# M700B.net
KiCad netlist of a schematic drawn in EAGLE
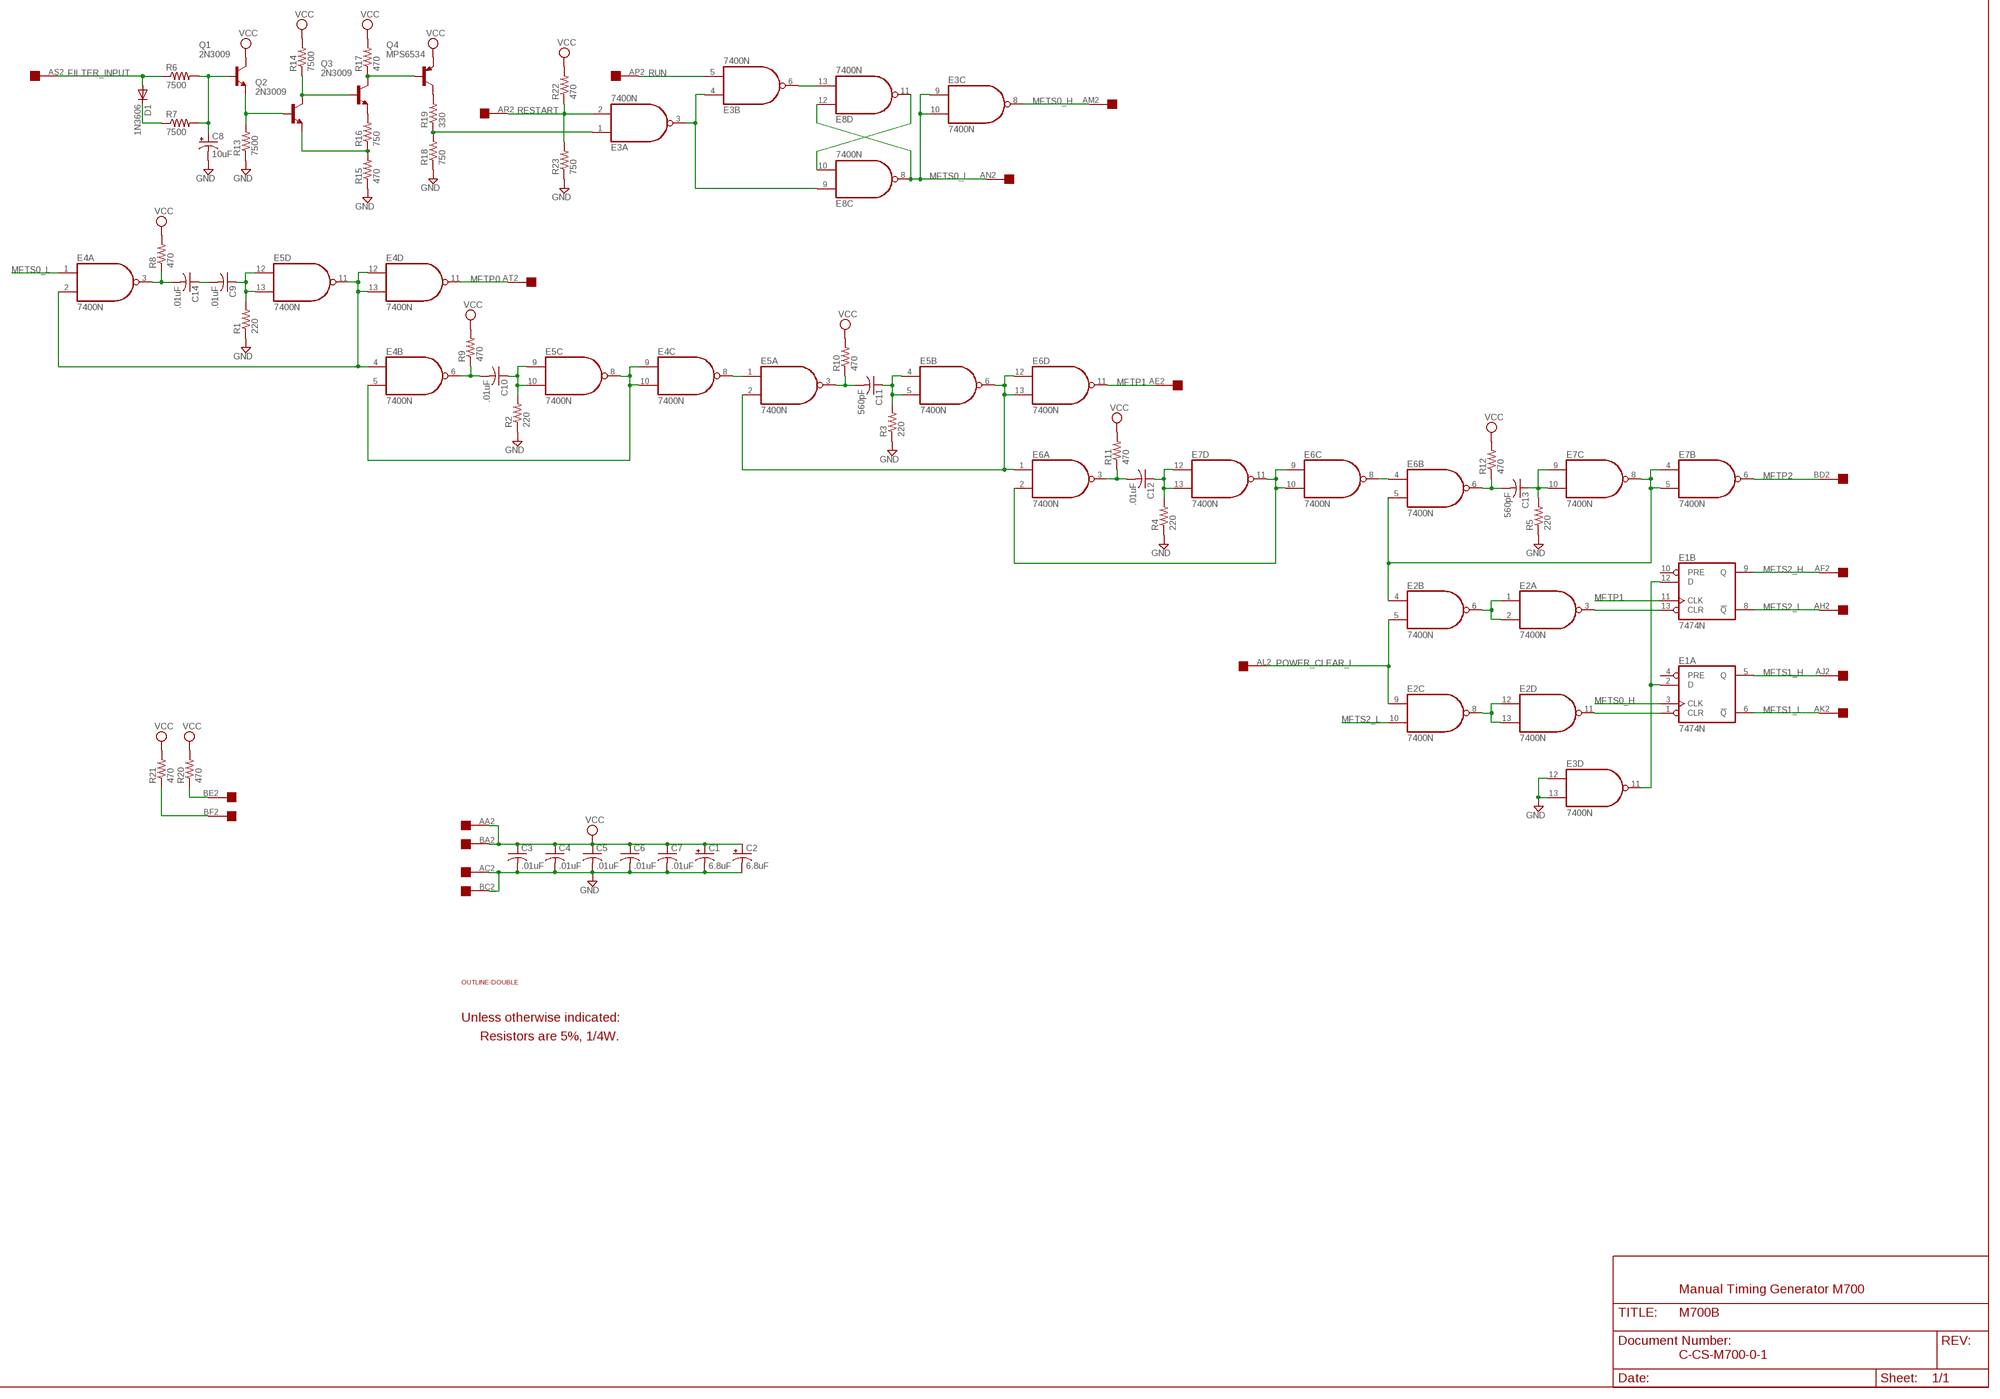
[diagram p0: schematic, sheet 1]

(export (version "E")
  (design (tool "Eeschema 10.0.6"))
  (components
    (comp (ref "C1")
      (value "6.8uF")
      (footprint "eagle-import:E12-8")
      (libsource (lib "eagle-import") (part "CPOL-USE20-8AXIAL"))
    )
    (comp (ref "C2")
      (value "6.8uF")
      (footprint "eagle-import:E12-8")
      (libsource (lib "eagle-import") (part "CPOL-USE20-8AXIAL"))
    )
    (comp (ref "C3")
      (value ".01uF")
      (footprint "eagle-import:C050-025X075")
      (libsource (lib "eagle-import") (part "C-US050-025X075"))
    )
    (comp (ref "C4")
      (value ".01uF")
      (footprint "eagle-import:C050-025X075")
      (libsource (lib "eagle-import") (part "C-US050-025X075"))
    )
    (comp (ref "C5")
      (value ".01uF")
      (footprint "eagle-import:C050-025X075")
      (libsource (lib "eagle-import") (part "C-US050-025X075"))
    )
    (comp (ref "C6")
      (value ".01uF")
      (footprint "eagle-import:C050-025X075")
      (libsource (lib "eagle-import") (part "C-US050-025X075"))
    )
    (comp (ref "C7")
      (value ".01uF")
      (footprint "eagle-import:C050-025X075")
      (libsource (lib "eagle-import") (part "C-US050-025X075"))
    )
    (comp (ref "C8")
      (value "10uF")
      (footprint "eagle-import:E12-8")
      (libsource (lib "eagle-import") (part "CPOL-USE20-8AXIAL"))
    )
    (comp (ref "C9")
      (value ".01uF")
      (footprint "eagle-import:C050-025X075")
      (libsource (lib "eagle-import") (part "C-US050-025X075"))
    )
    (comp (ref "C10")
      (value ".01uF")
      (footprint "eagle-import:C050-025X075")
      (libsource (lib "eagle-import") (part "C-US050-025X075"))
    )
    (comp (ref "C11")
      (value "560pF")
      (footprint "eagle-import:C050-025X075")
      (libsource (lib "eagle-import") (part "C-US050-025X075"))
    )
    (comp (ref "C12")
      (value ".01uF")
      (footprint "eagle-import:C050-025X075")
      (libsource (lib "eagle-import") (part "C-US050-025X075"))
    )
    (comp (ref "C13")
      (value "560pF")
      (footprint "eagle-import:C050-025X075")
      (libsource (lib "eagle-import") (part "C-US050-025X075"))
    )
    (comp (ref "C14")
      (value ".01uF")
      (footprint "eagle-import:C050-025X075")
      (libsource (lib "eagle-import") (part "C-US050-025X075"))
    )
    (comp (ref "D1")
      (value "1N3606")
      (footprint "eagle-import:DO35-10")
      (libsource (lib "eagle-import") (part "1N4148DO35-10"))
    )
    (comp (ref "E1")
      (value "7474N")
      (footprint "eagle-import:DIL14")
      (libsource (lib "eagle-import") (part "7474NS"))
    )
    (comp (ref "E2")
      (value "7400N")
      (footprint "eagle-import:DIL14")
      (libsource (lib "eagle-import") (part "7400N"))
    )
    (comp (ref "E3")
      (value "7400N")
      (footprint "eagle-import:DIL14")
      (libsource (lib "eagle-import") (part "7400N"))
    )
    (comp (ref "E4")
      (value "7400N")
      (footprint "eagle-import:DIL14")
      (libsource (lib "eagle-import") (part "7400N"))
    )
    (comp (ref "E5")
      (value "7400N")
      (footprint "eagle-import:DIL14")
      (libsource (lib "eagle-import") (part "7400N"))
    )
    (comp (ref "E6")
      (value "7400N")
      (footprint "eagle-import:DIL14")
      (libsource (lib "eagle-import") (part "7400N"))
    )
    (comp (ref "E7")
      (value "7400N")
      (footprint "eagle-import:DIL14")
      (libsource (lib "eagle-import") (part "7400N"))
    )
    (comp (ref "E8")
      (value "7400N")
      (footprint "eagle-import:DIL14")
      (libsource (lib "eagle-import") (part "7400N"))
    )
    (comp (ref "Q1")
      (value "2N3009")
      (footprint "eagle-import:TO5")
      (libsource (lib "eagle-import") (part "2N2102"))
    )
    (comp (ref "Q2")
      (value "2N3009")
      (footprint "eagle-import:TO5")
      (libsource (lib "eagle-import") (part "2N2102"))
    )
    (comp (ref "Q3")
      (value "2N3009")
      (footprint "eagle-import:TO5")
      (libsource (lib "eagle-import") (part "2N2102"))
    )
    (comp (ref "Q4")
      (value "MPS6534")
      (footprint "eagle-import:TO5")
      (libsource (lib "eagle-import") (part "2N2905"))
    )
    (comp (ref "R1")
      (value "220")
      (footprint "eagle-import:0207_10")
      (libsource (lib "eagle-import") (part "R-US_0207/10"))
    )
    (comp (ref "R2")
      (value "220")
      (footprint "eagle-import:0207_10")
      (libsource (lib "eagle-import") (part "R-US_0207/10"))
    )
    (comp (ref "R3")
      (value "220")
      (footprint "eagle-import:0207_10")
      (libsource (lib "eagle-import") (part "R-US_0207/10"))
    )
    (comp (ref "R4")
      (value "220")
      (footprint "eagle-import:0207_10")
      (libsource (lib "eagle-import") (part "R-US_0207/10"))
    )
    (comp (ref "R5")
      (value "220")
      (footprint "eagle-import:0207_10")
      (libsource (lib "eagle-import") (part "R-US_0207/10"))
    )
    (comp (ref "R6")
      (value "7500")
      (footprint "eagle-import:0207_10")
      (libsource (lib "eagle-import") (part "R-US_0207/10"))
    )
    (comp (ref "R7")
      (value "7500")
      (footprint "eagle-import:0207_10")
      (libsource (lib "eagle-import") (part "R-US_0207/10"))
    )
    (comp (ref "R8")
      (value "470")
      (footprint "eagle-import:0207_10")
      (libsource (lib "eagle-import") (part "R-US_0207/10"))
    )
    (comp (ref "R9")
      (value "470")
      (footprint "eagle-import:0207_10")
      (libsource (lib "eagle-import") (part "R-US_0207/10"))
    )
    (comp (ref "R10")
      (value "470")
      (footprint "eagle-import:0207_10")
      (libsource (lib "eagle-import") (part "R-US_0207/10"))
    )
    (comp (ref "R11")
      (value "470")
      (footprint "eagle-import:0207_10")
      (libsource (lib "eagle-import") (part "R-US_0207/10"))
    )
    (comp (ref "R12")
      (value "470")
      (footprint "eagle-import:0207_10")
      (libsource (lib "eagle-import") (part "R-US_0207/10"))
    )
    (comp (ref "R13")
      (value "7500")
      (footprint "eagle-import:0207_10")
      (libsource (lib "eagle-import") (part "R-US_0207/10"))
    )
    (comp (ref "R14")
      (value "7500")
      (footprint "eagle-import:0207_10")
      (libsource (lib "eagle-import") (part "R-US_0207/10"))
    )
    (comp (ref "R15")
      (value "470")
      (footprint "eagle-import:0207_10")
      (libsource (lib "eagle-import") (part "R-US_0207/10"))
    )
    (comp (ref "R16")
      (value "750")
      (footprint "eagle-import:0207_10")
      (libsource (lib "eagle-import") (part "R-US_0207/10"))
    )
    (comp (ref "R17")
      (value "470")
      (footprint "eagle-import:0207_10")
      (libsource (lib "eagle-import") (part "R-US_0207/10"))
    )
    (comp (ref "R18")
      (value "750")
      (footprint "eagle-import:0207_10")
      (libsource (lib "eagle-import") (part "R-US_0207/10"))
    )
    (comp (ref "R19")
      (value "330")
      (footprint "eagle-import:0207_10")
      (libsource (lib "eagle-import") (part "R-US_0207/10"))
    )
    (comp (ref "R20")
      (value "470")
      (footprint "eagle-import:0207_10")
      (libsource (lib "eagle-import") (part "R-US_0207/10"))
    )
    (comp (ref "R21")
      (value "470")
      (footprint "eagle-import:0207_10")
      (libsource (lib "eagle-import") (part "R-US_0207/10"))
    )
    (comp (ref "R22")
      (value "470")
      (footprint "eagle-import:0207_10")
      (libsource (lib "eagle-import") (part "R-US_0207/10"))
    )
    (comp (ref "R23")
      (value "750")
      (footprint "eagle-import:0207_10")
      (libsource (lib "eagle-import") (part "R-US_0207/10"))
    )
    (comp (ref "U$1")
      (value "DOUBLE")
      (footprint "eagle-import:EDGE-CON4")
      (libsource (lib "eagle-import") (part "DOUBLE"))
    )
    (comp (ref "U$2")
      (value "OUTLINE-DOUBLE")
      (footprint "eagle-import:DOUBLE")
      (libsource (lib "eagle-import") (part "OUTLINE-DOUBLE"))
    )
  )
  (nets
    (net (code "1") (name "/FILTER_INPUT") (class "Default")
      (node (ref "D1") (pin "A") (pinfunction "A_A") (pintype "passive"))
      (node (ref "R6") (pin "1") (pinfunction "1_1") (pintype "passive"))
      (node (ref "U$1") (pin "AS2") (pinfunction "1_AS2") (pintype "bidirectional"))
    )
    (net (code "2") (name "/MFTP0") (class "Default")
      (node (ref "E4") (pin "11") (pinfunction "O_11") (pintype "output"))
      (node (ref "U$1") (pin "AT2") (pinfunction "1_AT2") (pintype "bidirectional"))
    )
    (net (code "3") (name "/MFTP1") (class "Default")
      (node (ref "E1") (pin "11") (pinfunction "CLK_11") (pintype "input"))
      (node (ref "E6") (pin "11") (pinfunction "O_11") (pintype "output"))
      (node (ref "U$1") (pin "AE2") (pinfunction "1_AE2") (pintype "bidirectional"))
    )
    (net (code "4") (name "/MFTP2") (class "Default")
      (node (ref "E7") (pin "6") (pinfunction "O_6") (pintype "output"))
      (node (ref "U$1") (pin "BD2") (pinfunction "1_BD2") (pintype "bidirectional"))
    )
    (net (code "5") (name "/MFTS0_H") (class "Default")
      (node (ref "E1") (pin "3") (pinfunction "CLK_3") (pintype "input"))
      (node (ref "E3") (pin "8") (pinfunction "O_8") (pintype "output"))
      (node (ref "U$1") (pin "AM2") (pinfunction "1_AM2") (pintype "bidirectional"))
    )
    (net (code "6") (name "/MFTS0_L") (class "Default")
      (node (ref "E3") (pin "10") (pinfunction "I1_10") (pintype "input"))
      (node (ref "E3") (pin "9") (pinfunction "I0_9") (pintype "input"))
      (node (ref "E4") (pin "1") (pinfunction "I0_1") (pintype "input"))
      (node (ref "E8") (pin "12") (pinfunction "I0_12") (pintype "input"))
      (node (ref "E8") (pin "8") (pinfunction "O_8") (pintype "output"))
      (node (ref "U$1") (pin "AN2") (pinfunction "1_AN2") (pintype "bidirectional"))
    )
    (net (code "7") (name "/MFTS1_H") (class "Default")
      (node (ref "E1") (pin "5") (pinfunction "Q_5") (pintype "output"))
      (node (ref "U$1") (pin "AJ2") (pinfunction "1_AJ2") (pintype "bidirectional"))
    )
    (net (code "8") (name "/MFTS1_L") (class "Default")
      (node (ref "E1") (pin "6") (pinfunction "~{Q}_6") (pintype "output"))
      (node (ref "U$1") (pin "AK2") (pinfunction "1_AK2") (pintype "bidirectional"))
    )
    (net (code "9") (name "/MFTS2_H") (class "Default")
      (node (ref "E1") (pin "9") (pinfunction "Q_9") (pintype "output"))
      (node (ref "U$1") (pin "AF2") (pinfunction "1_AF2") (pintype "bidirectional"))
    )
    (net (code "10") (name "/MFTS2_L") (class "Default")
      (node (ref "E1") (pin "8") (pinfunction "~{Q}_8") (pintype "output"))
      (node (ref "E2") (pin "10") (pinfunction "I1_10") (pintype "input"))
      (node (ref "U$1") (pin "AH2") (pinfunction "1_AH2") (pintype "bidirectional"))
    )
    (net (code "11") (name "/POWER_CLEAR_L") (class "Default")
      (node (ref "E2") (pin "5") (pinfunction "I1_5") (pintype "input"))
      (node (ref "E2") (pin "9") (pinfunction "I0_9") (pintype "input"))
      (node (ref "U$1") (pin "AL2") (pinfunction "1_AL2") (pintype "bidirectional"))
    )
    (net (code "12") (name "/RESTART") (class "Default")
      (node (ref "E3") (pin "2") (pinfunction "I1_2") (pintype "input"))
      (node (ref "R22") (pin "1") (pinfunction "1_1") (pintype "passive"))
      (node (ref "R23") (pin "2") (pinfunction "2_2") (pintype "passive"))
      (node (ref "U$1") (pin "AR2") (pinfunction "1_AR2") (pintype "bidirectional"))
    )
    (net (code "13") (name "/RUN") (class "Default")
      (node (ref "E3") (pin "5") (pinfunction "I1_5") (pintype "input"))
      (node (ref "U$1") (pin "AP2") (pinfunction "1_AP2") (pintype "bidirectional"))
    )
    (net (code "14") (name "GND") (class "Default")
      (node (ref "C1") (pin "-") (pinfunction "-_-") (pintype "passive"))
      (node (ref "C2") (pin "-") (pinfunction "-_-") (pintype "passive"))
      (node (ref "C3") (pin "2") (pinfunction "2_2") (pintype "passive"))
      (node (ref "C4") (pin "2") (pinfunction "2_2") (pintype "passive"))
      (node (ref "C5") (pin "2") (pinfunction "2_2") (pintype "passive"))
      (node (ref "C6") (pin "2") (pinfunction "2_2") (pintype "passive"))
      (node (ref "C7") (pin "2") (pinfunction "2_2") (pintype "passive"))
      (node (ref "C8") (pin "-") (pinfunction "-_-") (pintype "passive"))
      (node (ref "E3") (pin "12") (pinfunction "I0_12") (pintype "input"))
      (node (ref "E3") (pin "13") (pinfunction "I1_13") (pintype "input"))
      (node (ref "R1") (pin "1") (pinfunction "1_1") (pintype "passive"))
      (node (ref "R13") (pin "1") (pinfunction "1_1") (pintype "passive"))
      (node (ref "R15") (pin "1") (pinfunction "1_1") (pintype "passive"))
      (node (ref "R18") (pin "1") (pinfunction "1_1") (pintype "passive"))
      (node (ref "R2") (pin "1") (pinfunction "1_1") (pintype "passive"))
      (node (ref "R23") (pin "1") (pinfunction "1_1") (pintype "passive"))
      (node (ref "R3") (pin "1") (pinfunction "1_1") (pintype "passive"))
      (node (ref "R4") (pin "1") (pinfunction "1_1") (pintype "passive"))
      (node (ref "R5") (pin "1") (pinfunction "1_1") (pintype "passive"))
      (node (ref "U$1") (pin "AC2") (pinfunction "1_AC2") (pintype "bidirectional"))
      (node (ref "U$1") (pin "BC2") (pinfunction "1_BC2") (pintype "bidirectional"))
    )
    (net (code "15") (name "Net-(C14-Pad1)") (class "Default")
      (node (ref "C14") (pin "1") (pinfunction "1_1") (pintype "passive"))
      (node (ref "C9") (pin "2") (pinfunction "2_2") (pintype "passive"))
    )
    (net (code "16") (name "Net-(D1-PadC)") (class "Default")
      (node (ref "D1") (pin "C") (pinfunction "C_C") (pintype "passive"))
      (node (ref "R7") (pin "1") (pinfunction "1_1") (pintype "passive"))
    )
    (net (code "17") (name "Net-(E1A-CLR)") (class "Default")
      (node (ref "E1") (pin "1") (pinfunction "CLR_1") (pintype "input"))
      (node (ref "E2") (pin "11") (pinfunction "O_11") (pintype "output"))
    )
    (net (code "18") (name "Net-(E1A-D)") (class "Default")
      (node (ref "E1") (pin "12") (pinfunction "D_12") (pintype "input"))
      (node (ref "E1") (pin "2") (pinfunction "D_2") (pintype "input"))
      (node (ref "E3") (pin "11") (pinfunction "O_11") (pintype "output"))
    )
    (net (code "19") (name "Net-(E1B-CLR)") (class "Default")
      (node (ref "E1") (pin "13") (pinfunction "CLR_13") (pintype "input"))
      (node (ref "E2") (pin "3") (pinfunction "O_3") (pintype "output"))
    )
    (net (code "20") (name "Net-(E2A-I0)") (class "Default")
      (node (ref "E2") (pin "1") (pinfunction "I0_1") (pintype "input"))
      (node (ref "E2") (pin "2") (pinfunction "I1_2") (pintype "input"))
      (node (ref "E2") (pin "6") (pinfunction "O_6") (pintype "output"))
    )
    (net (code "21") (name "Net-(E2B-I0)") (class "Default")
      (node (ref "E2") (pin "4") (pinfunction "I0_4") (pintype "input"))
      (node (ref "E6") (pin "5") (pinfunction "I1_5") (pintype "input"))
      (node (ref "E7") (pin "4") (pinfunction "I0_4") (pintype "input"))
      (node (ref "E7") (pin "5") (pinfunction "I1_5") (pintype "input"))
      (node (ref "E7") (pin "8") (pinfunction "O_8") (pintype "output"))
    )
    (net (code "22") (name "Net-(E2C-O)") (class "Default")
      (node (ref "E2") (pin "12") (pinfunction "I0_12") (pintype "input"))
      (node (ref "E2") (pin "13") (pinfunction "I1_13") (pintype "input"))
      (node (ref "E2") (pin "8") (pinfunction "O_8") (pintype "output"))
    )
    (net (code "23") (name "Net-(E3A-I0)") (class "Default")
      (node (ref "E3") (pin "1") (pinfunction "I0_1") (pintype "input"))
      (node (ref "R18") (pin "2") (pinfunction "2_2") (pintype "passive"))
      (node (ref "R19") (pin "1") (pinfunction "1_1") (pintype "passive"))
    )
    (net (code "24") (name "Net-(E3A-O)") (class "Default")
      (node (ref "E3") (pin "3") (pinfunction "O_3") (pintype "output"))
      (node (ref "E3") (pin "4") (pinfunction "I0_4") (pintype "input"))
      (node (ref "E8") (pin "9") (pinfunction "I0_9") (pintype "input"))
    )
    (net (code "25") (name "Net-(E3B-O)") (class "Default")
      (node (ref "E3") (pin "6") (pinfunction "O_6") (pintype "output"))
      (node (ref "E8") (pin "13") (pinfunction "I1_13") (pintype "input"))
    )
    (net (code "26") (name "Net-(E4A-I1)") (class "Default")
      (node (ref "E4") (pin "12") (pinfunction "I0_12") (pintype "input"))
      (node (ref "E4") (pin "13") (pinfunction "I1_13") (pintype "input"))
      (node (ref "E4") (pin "2") (pinfunction "I1_2") (pintype "input"))
      (node (ref "E4") (pin "4") (pinfunction "I0_4") (pintype "input"))
      (node (ref "E5") (pin "11") (pinfunction "O_11") (pintype "output"))
    )
    (net (code "27") (name "Net-(E4A-O)") (class "Default")
      (node (ref "C14") (pin "2") (pinfunction "2_2") (pintype "passive"))
      (node (ref "E4") (pin "3") (pinfunction "O_3") (pintype "output"))
      (node (ref "R8") (pin "1") (pinfunction "1_1") (pintype "passive"))
    )
    (net (code "28") (name "Net-(E4B-I1)") (class "Default")
      (node (ref "E4") (pin "10") (pinfunction "I1_10") (pintype "input"))
      (node (ref "E4") (pin "5") (pinfunction "I1_5") (pintype "input"))
      (node (ref "E4") (pin "9") (pinfunction "I0_9") (pintype "input"))
      (node (ref "E5") (pin "8") (pinfunction "O_8") (pintype "output"))
    )
    (net (code "29") (name "Net-(E4B-O)") (class "Default")
      (node (ref "C10") (pin "2") (pinfunction "2_2") (pintype "passive"))
      (node (ref "E4") (pin "6") (pinfunction "O_6") (pintype "output"))
      (node (ref "R9") (pin "1") (pinfunction "1_1") (pintype "passive"))
    )
    (net (code "30") (name "Net-(E4C-O)") (class "Default")
      (node (ref "E4") (pin "8") (pinfunction "O_8") (pintype "output"))
      (node (ref "E5") (pin "1") (pinfunction "I0_1") (pintype "input"))
    )
    (net (code "31") (name "Net-(E5A-I1)") (class "Default")
      (node (ref "E5") (pin "2") (pinfunction "I1_2") (pintype "input"))
      (node (ref "E5") (pin "6") (pinfunction "O_6") (pintype "output"))
      (node (ref "E6") (pin "1") (pinfunction "I0_1") (pintype "input"))
      (node (ref "E6") (pin "12") (pinfunction "I0_12") (pintype "input"))
      (node (ref "E6") (pin "13") (pinfunction "I1_13") (pintype "input"))
    )
    (net (code "32") (name "Net-(E5A-O)") (class "Default")
      (node (ref "C11") (pin "2") (pinfunction "2_2") (pintype "passive"))
      (node (ref "E5") (pin "3") (pinfunction "O_3") (pintype "output"))
      (node (ref "R10") (pin "1") (pinfunction "1_1") (pintype "passive"))
    )
    (net (code "33") (name "Net-(E5B-I0)") (class "Default")
      (node (ref "C11") (pin "1") (pinfunction "1_1") (pintype "passive"))
      (node (ref "E5") (pin "4") (pinfunction "I0_4") (pintype "input"))
      (node (ref "E5") (pin "5") (pinfunction "I1_5") (pintype "input"))
      (node (ref "R3") (pin "2") (pinfunction "2_2") (pintype "passive"))
    )
    (net (code "34") (name "Net-(E5C-I0)") (class "Default")
      (node (ref "C10") (pin "1") (pinfunction "1_1") (pintype "passive"))
      (node (ref "E5") (pin "10") (pinfunction "I1_10") (pintype "input"))
      (node (ref "E5") (pin "9") (pinfunction "I0_9") (pintype "input"))
      (node (ref "R2") (pin "2") (pinfunction "2_2") (pintype "passive"))
    )
    (net (code "35") (name "Net-(E5D-I0)") (class "Default")
      (node (ref "C9") (pin "1") (pinfunction "1_1") (pintype "passive"))
      (node (ref "E5") (pin "12") (pinfunction "I0_12") (pintype "input"))
      (node (ref "E5") (pin "13") (pinfunction "I1_13") (pintype "input"))
      (node (ref "R1") (pin "2") (pinfunction "2_2") (pintype "passive"))
    )
    (net (code "36") (name "Net-(E6A-I1)") (class "Default")
      (node (ref "E6") (pin "10") (pinfunction "I1_10") (pintype "input"))
      (node (ref "E6") (pin "2") (pinfunction "I1_2") (pintype "input"))
      (node (ref "E6") (pin "9") (pinfunction "I0_9") (pintype "input"))
      (node (ref "E7") (pin "11") (pinfunction "O_11") (pintype "output"))
    )
    (net (code "37") (name "Net-(E6A-O)") (class "Default")
      (node (ref "C12") (pin "2") (pinfunction "2_2") (pintype "passive"))
      (node (ref "E6") (pin "3") (pinfunction "O_3") (pintype "output"))
      (node (ref "R11") (pin "1") (pinfunction "1_1") (pintype "passive"))
    )
    (net (code "38") (name "Net-(E6B-I0)") (class "Default")
      (node (ref "E6") (pin "4") (pinfunction "I0_4") (pintype "input"))
      (node (ref "E6") (pin "8") (pinfunction "O_8") (pintype "output"))
    )
    (net (code "39") (name "Net-(E6B-O)") (class "Default")
      (node (ref "C13") (pin "2") (pinfunction "2_2") (pintype "passive"))
      (node (ref "E6") (pin "6") (pinfunction "O_6") (pintype "output"))
      (node (ref "R12") (pin "1") (pinfunction "1_1") (pintype "passive"))
    )
    (net (code "40") (name "Net-(E7C-I0)") (class "Default")
      (node (ref "C13") (pin "1") (pinfunction "1_1") (pintype "passive"))
      (node (ref "E7") (pin "10") (pinfunction "I1_10") (pintype "input"))
      (node (ref "E7") (pin "9") (pinfunction "I0_9") (pintype "input"))
      (node (ref "R5") (pin "2") (pinfunction "2_2") (pintype "passive"))
    )
    (net (code "41") (name "Net-(E7D-I0)") (class "Default")
      (node (ref "C12") (pin "1") (pinfunction "1_1") (pintype "passive"))
      (node (ref "E7") (pin "12") (pinfunction "I0_12") (pintype "input"))
      (node (ref "E7") (pin "13") (pinfunction "I1_13") (pintype "input"))
      (node (ref "R4") (pin "2") (pinfunction "2_2") (pintype "passive"))
    )
    (net (code "42") (name "Net-(E8C-I1)") (class "Default")
      (node (ref "E8") (pin "10") (pinfunction "I1_10") (pintype "input"))
      (node (ref "E8") (pin "11") (pinfunction "O_11") (pintype "output"))
    )
    (net (code "43") (name "Net-(Q1-B)") (class "Default")
      (node (ref "C8") (pin "+") (pinfunction "+_+") (pintype "passive"))
      (node (ref "Q1") (pin "2") (pinfunction "B_2") (pintype "passive"))
      (node (ref "R6") (pin "2") (pinfunction "2_2") (pintype "passive"))
      (node (ref "R7") (pin "2") (pinfunction "2_2") (pintype "passive"))
    )
    (net (code "44") (name "Net-(Q1-E)") (class "Default")
      (node (ref "Q1") (pin "1") (pinfunction "E_1") (pintype "passive"))
      (node (ref "Q2") (pin "2") (pinfunction "B_2") (pintype "passive"))
      (node (ref "R13") (pin "2") (pinfunction "2_2") (pintype "passive"))
    )
    (net (code "45") (name "Net-(Q2-C)") (class "Default")
      (node (ref "Q2") (pin "3") (pinfunction "C_3") (pintype "passive"))
      (node (ref "Q3") (pin "2") (pinfunction "B_2") (pintype "passive"))
      (node (ref "R14") (pin "1") (pinfunction "1_1") (pintype "passive"))
    )
    (net (code "46") (name "Net-(Q2-E)") (class "Default")
      (node (ref "Q2") (pin "1") (pinfunction "E_1") (pintype "passive"))
      (node (ref "R15") (pin "2") (pinfunction "2_2") (pintype "passive"))
      (node (ref "R16") (pin "1") (pinfunction "1_1") (pintype "passive"))
    )
    (net (code "47") (name "Net-(Q3-C)") (class "Default")
      (node (ref "Q3") (pin "3") (pinfunction "C_3") (pintype "passive"))
      (node (ref "Q4") (pin "2") (pinfunction "B_2") (pintype "passive"))
      (node (ref "R17") (pin "1") (pinfunction "1_1") (pintype "passive"))
    )
    (net (code "48") (name "Net-(Q3-E)") (class "Default")
      (node (ref "Q3") (pin "1") (pinfunction "E_1") (pintype "passive"))
      (node (ref "R16") (pin "2") (pinfunction "2_2") (pintype "passive"))
    )
    (net (code "49") (name "Net-(Q4-C)") (class "Default")
      (node (ref "Q4") (pin "3") (pinfunction "C_3") (pintype "passive"))
      (node (ref "R19") (pin "2") (pinfunction "2_2") (pintype "passive"))
    )
    (net (code "50") (name "Net-(U$1AT-1)") (class "Default")
      (node (ref "R20") (pin "1") (pinfunction "1_1") (pintype "passive"))
      (node (ref "U$1") (pin "BE2") (pinfunction "1_BE2") (pintype "bidirectional"))
    )
    (net (code "51") (name "Net-(U$1AV-1)") (class "Default")
      (node (ref "R21") (pin "1") (pinfunction "1_1") (pintype "passive"))
      (node (ref "U$1") (pin "BF2") (pinfunction "1_BF2") (pintype "bidirectional"))
    )
    (net (code "52") (name "VCC") (class "Default")
      (node (ref "C1") (pin "+") (pinfunction "+_+") (pintype "passive"))
      (node (ref "C2") (pin "+") (pinfunction "+_+") (pintype "passive"))
      (node (ref "C3") (pin "1") (pinfunction "1_1") (pintype "passive"))
      (node (ref "C4") (pin "1") (pinfunction "1_1") (pintype "passive"))
      (node (ref "C5") (pin "1") (pinfunction "1_1") (pintype "passive"))
      (node (ref "C6") (pin "1") (pinfunction "1_1") (pintype "passive"))
      (node (ref "C7") (pin "1") (pinfunction "1_1") (pintype "passive"))
      (node (ref "Q1") (pin "3") (pinfunction "C_3") (pintype "passive"))
      (node (ref "Q4") (pin "1") (pinfunction "E_1") (pintype "passive"))
      (node (ref "R10") (pin "2") (pinfunction "2_2") (pintype "passive"))
      (node (ref "R11") (pin "2") (pinfunction "2_2") (pintype "passive"))
      (node (ref "R12") (pin "2") (pinfunction "2_2") (pintype "passive"))
      (node (ref "R14") (pin "2") (pinfunction "2_2") (pintype "passive"))
      (node (ref "R17") (pin "2") (pinfunction "2_2") (pintype "passive"))
      (node (ref "R20") (pin "2") (pinfunction "2_2") (pintype "passive"))
      (node (ref "R21") (pin "2") (pinfunction "2_2") (pintype "passive"))
      (node (ref "R22") (pin "2") (pinfunction "2_2") (pintype "passive"))
      (node (ref "R8") (pin "2") (pinfunction "2_2") (pintype "passive"))
      (node (ref "R9") (pin "2") (pinfunction "2_2") (pintype "passive"))
      (node (ref "U$1") (pin "AA2") (pinfunction "1_AA2") (pintype "bidirectional"))
      (node (ref "U$1") (pin "BA2") (pinfunction "1_BA2") (pintype "bidirectional"))
    )
    (net (code "53") (name "unconnected-(E1A-PRE-Pad4)") (class "Default")
      (node (ref "E1") (pin "4") (pinfunction "PRE_4") (pintype "input"))
    )
    (net (code "54") (name "unconnected-(E1B-PRE-Pad10)") (class "Default")
      (node (ref "E1") (pin "10") (pinfunction "PRE_10") (pintype "input"))
    )
  )
)
